# ESP32_PICO_D4.net
KiCad netlist of a schematic drawn in Altium Designer
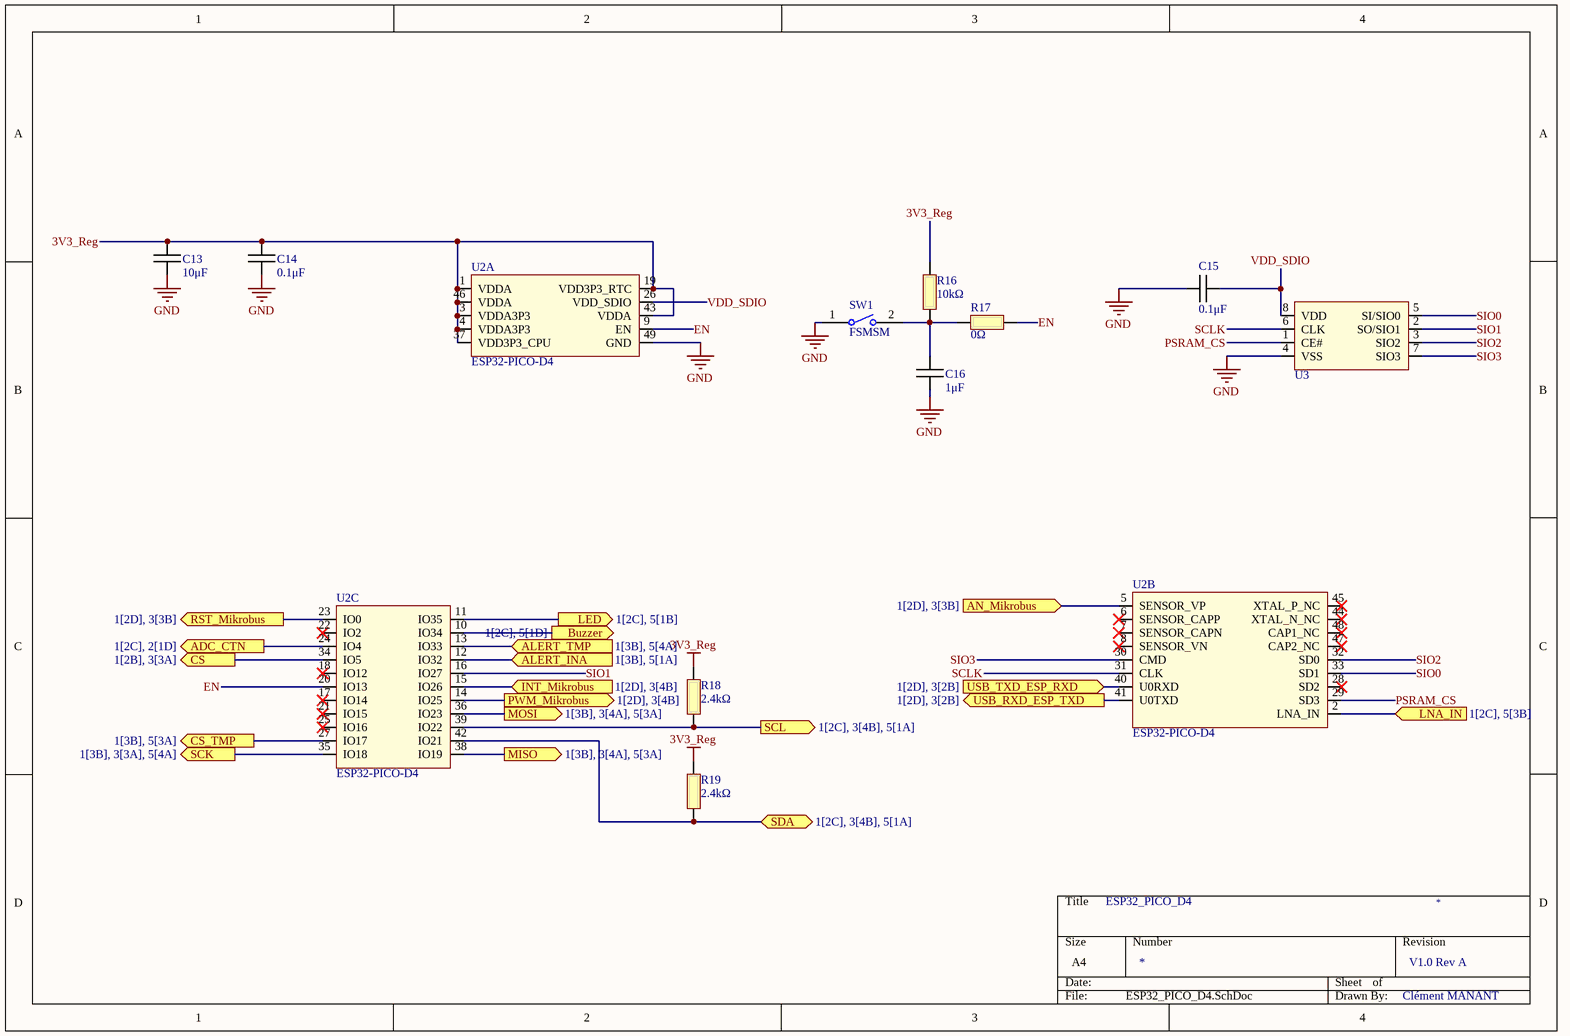
[diagram p0: ESP32_PICO_D4.SchDoc]

(export (version "E")
  (design (tool "Eeschema 10.0.6"))
  (components
    (comp (ref "C13")
      (value "10μF")
      (footprint "CAPC1005X06N")
      (libsource (lib "SCHLibrary") (part "Capacitor"))
    )
    (comp (ref "C14")
      (value "0.1μF")
      (footprint "CAPC1005X06N")
      (libsource (lib "SCHLibrary") (part "Capacitor"))
    )
    (comp (ref "C15")
      (value "0.1μF")
      (footprint "CAPC1005X06N")
      (libsource (lib "SCHLibrary") (part "Capacitor"))
    )
    (comp (ref "C16")
      (value "1μF")
      (footprint "CAPC1005X06N")
      (libsource (lib "SCHLibrary") (part "Capacitor"))
    )
    (comp (ref "R16")
      (value "10kΩ")
      (footprint "RESC1005X06N")
      (libsource (lib "SCHLibrary") (part "Resistor"))
    )
    (comp (ref "R17") (value "0Ω") (footprint "RESC1005X06N") (libsource (lib "") (part "Resistor_1")))
    (comp (ref "R18")
      (value "2.4kΩ")
      (footprint "RESC1005X06N")
      (libsource (lib "SCHLibrary") (part "Resistor"))
    )
    (comp (ref "R19")
      (value "2.4kΩ")
      (footprint "RESC1005X06N")
      (libsource (lib "SCHLibrary") (part "Resistor"))
    )
    (comp (ref "SW1")
      (value "FSMSM")
      (footprint "TECO-FSMSM-2_V")
      (description "FSMSM Push Button Switch, 50 mA, -35 to 85 degC, 2-Pin SMD, RoHS, Bulk")
      (fields (field (name "MANUFACTURER") "TE Connectivity"))
      (libsource (lib "SCHLibrary") (part "CMP-2000-07511-1"))
    )
    (comp (ref "U2")
      (value "ESP32-PICO-D4")
      (footprint "PQFN50P700X700X104_HS-49N")
      (libsource (lib "SCHLibrary") (part "ESP32"))
    )
    (comp (ref "U3")
      (value "IS66WVS1M8BLL-104NLI")
      (footprint "SOIC127P600X175-8N")
      (description "SRAM 8Mb, SerialRAM, 2.7V-3.6V, 104MHz, 8 pin SOIC 150 mil, RoHS")
      (libsource (lib "SCHLibrary") (part "SRAM"))
    )
  )
  (nets
    (net (code "1") (name "/ADC_CTN") (class "Default")
      (node (ref "U2") (pin "24") (pinfunction "IO4_24") (pintype "passive"))
    )
    (net (code "2") (name "/ALERT_INA") (class "Default")
      (node (ref "U2") (pin "12") (pinfunction "IO32_12") (pintype "passive"))
    )
    (net (code "3") (name "/ALERT_TMP") (class "Default")
      (node (ref "U2") (pin "13") (pinfunction "IO33_13") (pintype "passive"))
    )
    (net (code "4") (name "/AN_Mikrobus") (class "Default")
      (node (ref "U2") (pin "5") (pinfunction "SENSOR_VP_5") (pintype "passive"))
    )
    (net (code "5") (name "/Buzzer") (class "Default")
      (node (ref "U2") (pin "10") (pinfunction "IO34_10") (pintype "passive"))
    )
    (net (code "6") (name "/CS") (class "Default")
      (node (ref "U2") (pin "34") (pinfunction "IO5_34") (pintype "passive"))
    )
    (net (code "7") (name "/CS_TMP") (class "Default")
      (node (ref "U2") (pin "27") (pinfunction "IO17_27") (pintype "passive"))
    )
    (net (code "8") (name "/EN") (class "Default")
      (node (ref "R17") (pin "2") (pinfunction "2_2") (pintype "passive"))
      (node (ref "U2") (pin "20") (pinfunction "IO13_20") (pintype "passive"))
      (node (ref "U2") (pin "9") (pinfunction "EN_9") (pintype "passive"))
    )
    (net (code "9") (name "/INT_Mikrobus") (class "Default")
      (node (ref "U2") (pin "15") (pinfunction "IO26_15") (pintype "passive"))
    )
    (net (code "10") (name "/LED") (class "Default")
      (node (ref "U2") (pin "11") (pinfunction "IO35_11") (pintype "passive"))
    )
    (net (code "11") (name "/LNA_IN") (class "Default")
      (node (ref "U2") (pin "2") (pinfunction "LNA_IN_2") (pintype "passive"))
    )
    (net (code "12") (name "/MISO") (class "Default")
      (node (ref "U2") (pin "38") (pinfunction "IO19_38") (pintype "passive"))
    )
    (net (code "13") (name "/MOSI") (class "Default")
      (node (ref "U2") (pin "36") (pinfunction "IO23_36") (pintype "passive"))
    )
    (net (code "14") (name "/PSRAM_CS") (class "Default")
      (node (ref "U2") (pin "29") (pinfunction "SD3_29") (pintype "passive"))
      (node (ref "U3") (pin "1") (pinfunction "CE#_1") (pintype "passive"))
    )
    (net (code "15") (name "/PWM_Mikrobus") (class "Default")
      (node (ref "U2") (pin "14") (pinfunction "IO25_14") (pintype "passive"))
    )
    (net (code "16") (name "/RST_Mikrobus") (class "Default")
      (node (ref "U2") (pin "23") (pinfunction "IO0_23") (pintype "passive"))
    )
    (net (code "17") (name "/SCK") (class "Default")
      (node (ref "U2") (pin "35") (pinfunction "IO18_35") (pintype "passive"))
    )
    (net (code "18") (name "/SCL") (class "Default")
      (node (ref "R18") (pin "1") (pinfunction "1_1") (pintype "passive"))
      (node (ref "U2") (pin "39") (pinfunction "IO22_39") (pintype "passive"))
    )
    (net (code "19") (name "/SCLK") (class "Default")
      (node (ref "U2") (pin "31") (pinfunction "CLK_31") (pintype "passive"))
      (node (ref "U3") (pin "6") (pinfunction "CLK_6") (pintype "passive"))
    )
    (net (code "20") (name "/SDA") (class "Default")
      (node (ref "R19") (pin "1") (pinfunction "1_1") (pintype "passive"))
      (node (ref "U2") (pin "42") (pinfunction "IO21_42") (pintype "passive"))
    )
    (net (code "21") (name "/SIO0") (class "Default")
      (node (ref "U2") (pin "33") (pinfunction "SD1_33") (pintype "passive"))
      (node (ref "U3") (pin "5") (pinfunction "SI/SIO0_5") (pintype "passive"))
    )
    (net (code "22") (name "/SIO1") (class "Default")
      (node (ref "U2") (pin "16") (pinfunction "IO27_16") (pintype "passive"))
      (node (ref "U3") (pin "2") (pinfunction "SO/SIO1_2") (pintype "passive"))
    )
    (net (code "23") (name "/SIO2") (class "Default")
      (node (ref "U2") (pin "32") (pinfunction "SD0_32") (pintype "passive"))
      (node (ref "U3") (pin "3") (pinfunction "SIO2_3") (pintype "passive"))
    )
    (net (code "24") (name "/SIO3") (class "Default")
      (node (ref "U2") (pin "30") (pinfunction "CMD_30") (pintype "passive"))
      (node (ref "U3") (pin "7") (pinfunction "SIO3_7") (pintype "passive"))
    )
    (net (code "25") (name "/USB_RXD_ESP_TXD") (class "Default")
      (node (ref "U2") (pin "41") (pinfunction "U0TXD_41") (pintype "passive"))
    )
    (net (code "26") (name "/USB_TXD_ESP_RXD") (class "Default")
      (node (ref "U2") (pin "40") (pinfunction "U0RXD_40") (pintype "passive"))
    )
    (net (code "27") (name "/VDD_SDIO") (class "Default")
      (node (ref "C15") (pin "2") (pinfunction "2_2") (pintype "passive"))
      (node (ref "U2") (pin "26") (pinfunction "VDD_SDIO_26") (pintype "passive"))
      (node (ref "U3") (pin "8") (pinfunction "VDD_8") (pintype "passive"))
    )
    (net (code "28") (name "3V3_Reg") (class "Default")
      (node (ref "C13") (pin "1") (pinfunction "1_1") (pintype "passive"))
      (node (ref "C14") (pin "1") (pinfunction "1_1") (pintype "passive"))
      (node (ref "R16") (pin "2") (pinfunction "2_2") (pintype "passive"))
      (node (ref "R18") (pin "2") (pinfunction "2_2") (pintype "passive"))
      (node (ref "R19") (pin "2") (pinfunction "2_2") (pintype "passive"))
      (node (ref "U2") (pin "1") (pinfunction "VDDA_1") (pintype "passive"))
      (node (ref "U2") (pin "19") (pinfunction "VDD3P3_RTC_19") (pintype "passive"))
      (node (ref "U2") (pin "3") (pinfunction "VDDA3P3_3") (pintype "passive"))
      (node (ref "U2") (pin "37") (pinfunction "VDD3P3_CPU_37") (pintype "passive"))
      (node (ref "U2") (pin "4") (pinfunction "VDDA3P3_4") (pintype "passive"))
      (node (ref "U2") (pin "43") (pinfunction "VDDA_43") (pintype "passive"))
      (node (ref "U2") (pin "46") (pinfunction "VDDA_46") (pintype "passive"))
    )
    (net (code "29") (name "GND") (class "Default")
      (node (ref "C13") (pin "2") (pinfunction "2_2") (pintype "passive"))
      (node (ref "C14") (pin "2") (pinfunction "2_2") (pintype "passive"))
      (node (ref "C15") (pin "1") (pinfunction "1_1") (pintype "passive"))
      (node (ref "C16") (pin "2") (pinfunction "2_2") (pintype "passive"))
      (node (ref "SW1") (pin "1") (pinfunction "1_1") (pintype "passive"))
      (node (ref "U2") (pin "49") (pinfunction "GND_49") (pintype "passive"))
      (node (ref "U3") (pin "4") (pinfunction "VSS_4") (pintype "passive"))
    )
    (net (code "30") (name "Net-(C16-Pad1)") (class "Default")
      (node (ref "C16") (pin "1") (pinfunction "1_1") (pintype "passive"))
      (node (ref "R16") (pin "1") (pinfunction "1_1") (pintype "passive"))
      (node (ref "R17") (pin "1") (pinfunction "1_1") (pintype "passive"))
      (node (ref "SW1") (pin "2") (pinfunction "2_2") (pintype "passive"))
    )
    (net (code "31") (name "unconnected-(U2B-CAP1_NC-Pad48)") (class "Default")
      (node (ref "U2") (pin "48") (pinfunction "CAP1_NC_48") (pintype "passive+no_connect"))
    )
    (net (code "32") (name "unconnected-(U2B-CAP2_NC-Pad47)") (class "Default")
      (node (ref "U2") (pin "47") (pinfunction "CAP2_NC_47") (pintype "passive+no_connect"))
    )
    (net (code "33") (name "unconnected-(U2B-SD2-Pad28)") (class "Default")
      (node (ref "U2") (pin "28") (pinfunction "SD2_28") (pintype "passive+no_connect"))
    )
    (net (code "34") (name "unconnected-(U2B-SENSOR_CAPN-Pad7)") (class "Default")
      (node (ref "U2") (pin "7") (pinfunction "SENSOR_CAPN_7") (pintype "passive+no_connect"))
    )
    (net (code "35") (name "unconnected-(U2B-SENSOR_CAPP-Pad6)") (class "Default")
      (node (ref "U2") (pin "6") (pinfunction "SENSOR_CAPP_6") (pintype "passive+no_connect"))
    )
    (net (code "36") (name "unconnected-(U2B-SENSOR_VN-Pad8)") (class "Default")
      (node (ref "U2") (pin "8") (pinfunction "SENSOR_VN_8") (pintype "passive+no_connect"))
    )
    (net (code "37") (name "unconnected-(U2B-XTAL_N_NC-Pad44)") (class "Default")
      (node (ref "U2") (pin "44") (pinfunction "XTAL_N_NC_44") (pintype "passive+no_connect"))
    )
    (net (code "38") (name "unconnected-(U2B-XTAL_P_NC-Pad45)") (class "Default")
      (node (ref "U2") (pin "45") (pinfunction "XTAL_P_NC_45") (pintype "passive+no_connect"))
    )
    (net (code "39") (name "unconnected-(U2C-IO2-Pad22)") (class "Default")
      (node (ref "U2") (pin "22") (pinfunction "IO2_22") (pintype "passive+no_connect"))
    )
    (net (code "40") (name "unconnected-(U2C-IO12-Pad18)") (class "Default")
      (node (ref "U2") (pin "18") (pinfunction "IO12_18") (pintype "passive+no_connect"))
    )
    (net (code "41") (name "unconnected-(U2C-IO14-Pad17)") (class "Default")
      (node (ref "U2") (pin "17") (pinfunction "IO14_17") (pintype "passive+no_connect"))
    )
    (net (code "42") (name "unconnected-(U2C-IO15-Pad21)") (class "Default")
      (node (ref "U2") (pin "21") (pinfunction "IO15_21") (pintype "passive+no_connect"))
    )
    (net (code "43") (name "unconnected-(U2C-IO16-Pad25)") (class "Default")
      (node (ref "U2") (pin "25") (pinfunction "IO16_25") (pintype "passive+no_connect"))
    )
  )
)
